# ACNode0_3.net
KiCad netlist of a schematic drawn in EAGLE
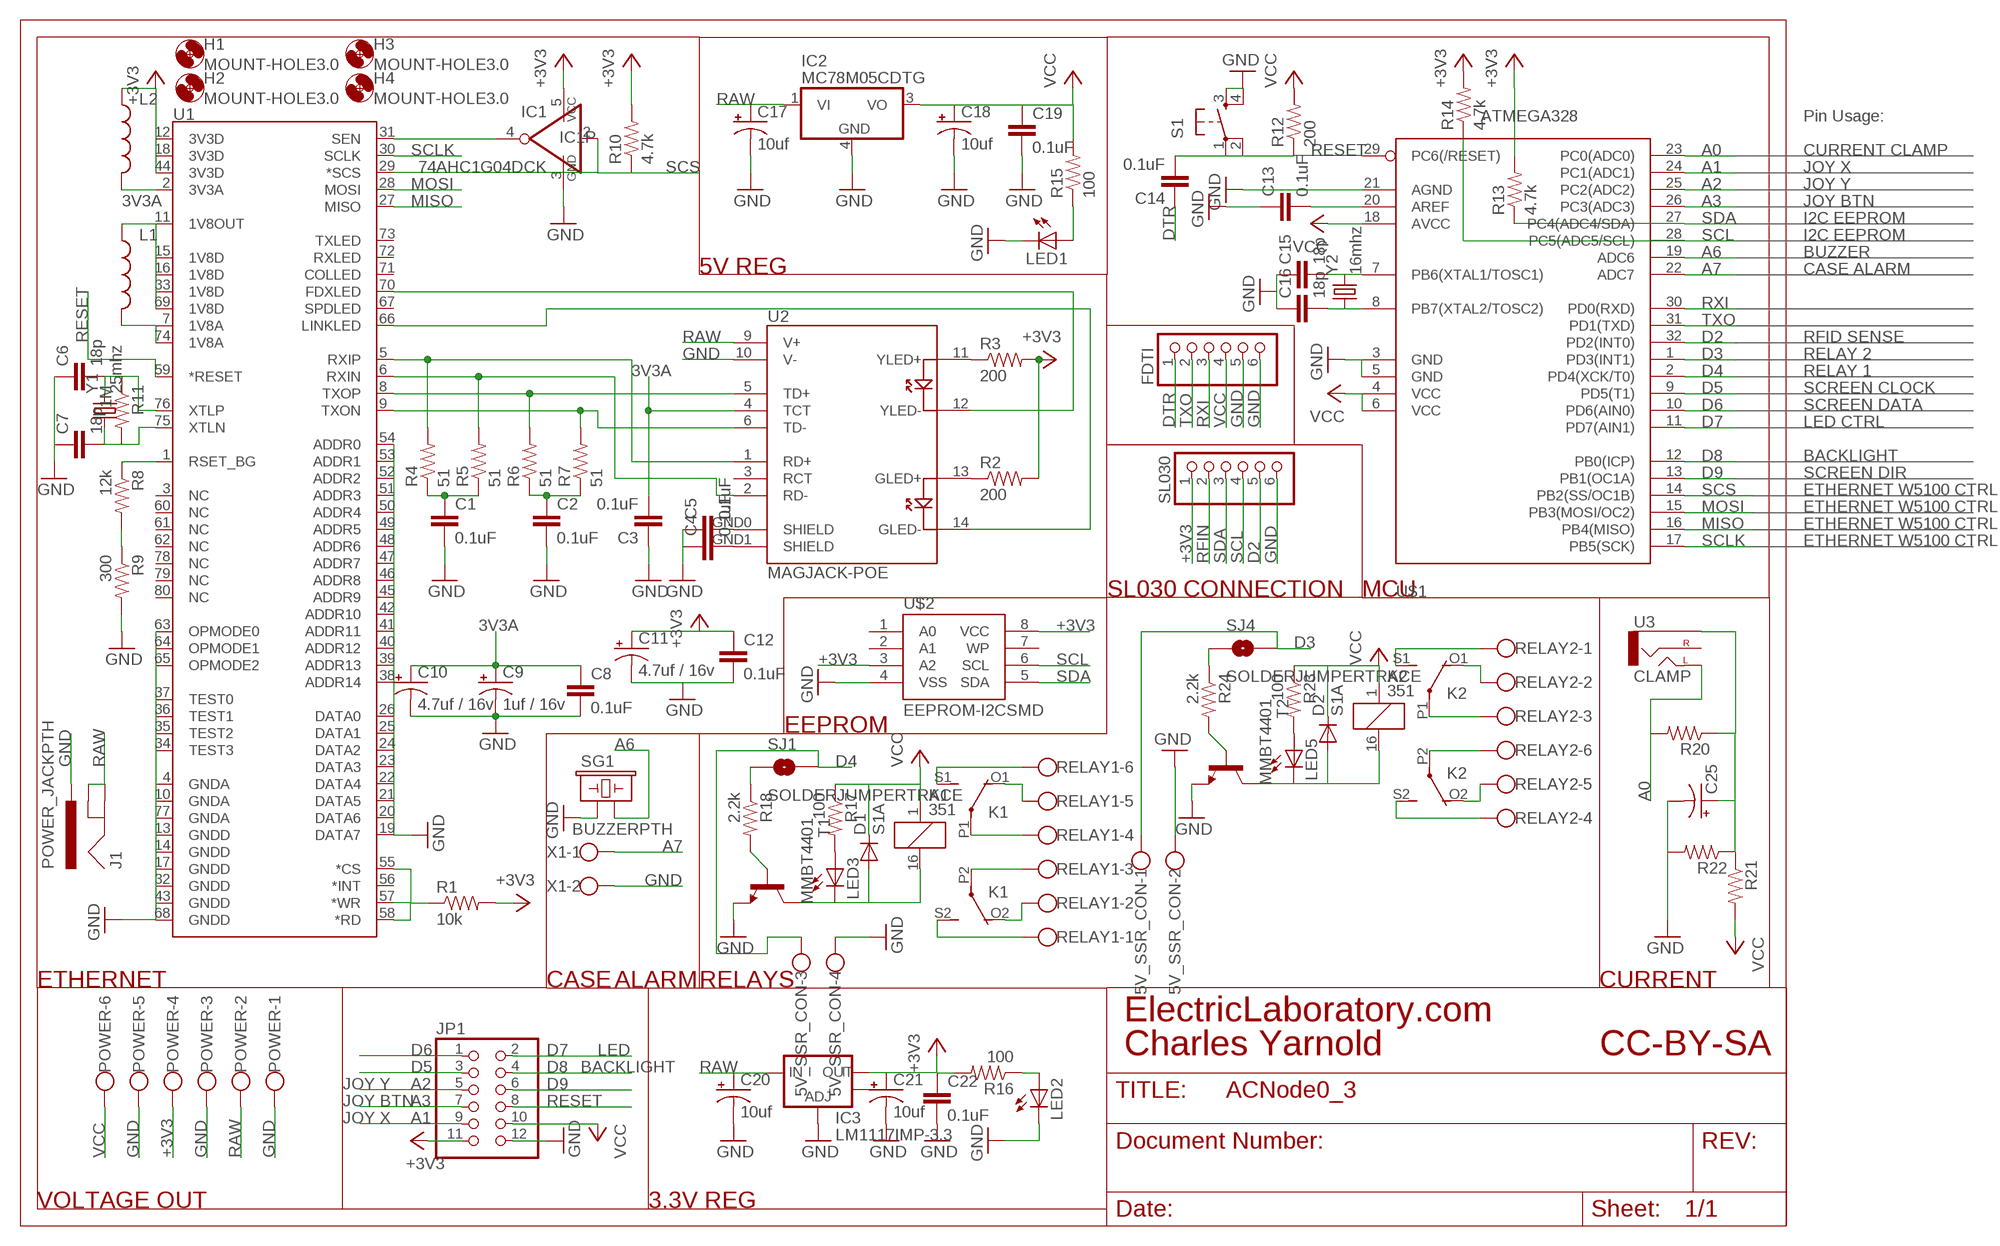
[diagram p0: schematic, sheet 1]

(export (version "E")
  (design (tool "Eeschema 10.0.6"))
  (components
    (comp (ref "5V_SSR_CON")
      (value "W237-4")
      (footprint "eagle-import:W237-4")
      (libsource (lib "eagle-import") (part "W237-4"))
    )
    (comp (ref "C1")
      (value "0.1uF")
      (footprint "eagle-import:0603-CAP")
      (libsource (lib "eagle-import") (part "CAP0603-CAP"))
    )
    (comp (ref "C2")
      (value "0.1uF")
      (footprint "eagle-import:0603-CAP")
      (libsource (lib "eagle-import") (part "CAP0603-CAP"))
    )
    (comp (ref "C3")
      (value "0.1uF")
      (footprint "eagle-import:0603-CAP")
      (libsource (lib "eagle-import") (part "CAP0603-CAP"))
    )
    (comp (ref "C4")
      (value "0.1uF")
      (footprint "eagle-import:0603-CAP")
      (libsource (lib "eagle-import") (part "CAP0603-CAP"))
    )
    (comp (ref "C5")
      (value "0.1uF")
      (footprint "eagle-import:0603-CAP")
      (libsource (lib "eagle-import") (part "CAP0603-CAP"))
    )
    (comp (ref "C6")
      (value "18p")
      (footprint "eagle-import:0603-CAP")
      (libsource (lib "eagle-import") (part "CAP0603-CAP"))
    )
    (comp (ref "C7")
      (value "18p")
      (footprint "eagle-import:0603-CAP")
      (libsource (lib "eagle-import") (part "CAP0603-CAP"))
    )
    (comp (ref "C8")
      (value "0.1uF")
      (footprint "eagle-import:0603-CAP")
      (libsource (lib "eagle-import") (part "CAP0603-CAP"))
    )
    (comp (ref "C9")
      (value "1uf / 16v")
      (footprint "eagle-import:EIA3216")
      (libsource (lib "eagle-import") (part "CAP_POL1206"))
    )
    (comp (ref "C10")
      (value "4.7uf / 16v")
      (footprint "eagle-import:EIA3216")
      (libsource (lib "eagle-import") (part "CAP_POL1206"))
    )
    (comp (ref "C11")
      (value "4.7uf / 16v")
      (footprint "eagle-import:EIA3216")
      (libsource (lib "eagle-import") (part "CAP_POL1206"))
    )
    (comp (ref "C12")
      (value "0.1uF")
      (footprint "eagle-import:0603-CAP")
      (libsource (lib "eagle-import") (part "CAP0603-CAP"))
    )
    (comp (ref "C13")
      (value "0.1uF")
      (footprint "eagle-import:0603-CAP")
      (libsource (lib "eagle-import") (part "CAP0603-CAP"))
    )
    (comp (ref "C14")
      (value "0.1uF")
      (footprint "eagle-import:0603-CAP")
      (libsource (lib "eagle-import") (part "CAP0603-CAP"))
    )
    (comp (ref "C15")
      (value "18p")
      (footprint "eagle-import:0603-CAP")
      (libsource (lib "eagle-import") (part "CAP0603-CAP"))
    )
    (comp (ref "C16")
      (value "18p")
      (footprint "eagle-import:0603-CAP")
      (libsource (lib "eagle-import") (part "CAP0603-CAP"))
    )
    (comp (ref "C17")
      (value "10uf")
      (footprint "eagle-import:EIA3216")
      (libsource (lib "eagle-import") (part "CAP_POL1206"))
    )
    (comp (ref "C18")
      (value "10uf")
      (footprint "eagle-import:EIA3216")
      (libsource (lib "eagle-import") (part "CAP_POL1206"))
    )
    (comp (ref "C19")
      (value "0.1uF")
      (footprint "eagle-import:0603-CAP")
      (libsource (lib "eagle-import") (part "CAP0603-CAP"))
    )
    (comp (ref "C20")
      (value "10uf")
      (footprint "eagle-import:EIA3216")
      (libsource (lib "eagle-import") (part "CAP_POL1206"))
    )
    (comp (ref "C21")
      (value "10uf")
      (footprint "eagle-import:EIA3216")
      (libsource (lib "eagle-import") (part "CAP_POL1206"))
    )
    (comp (ref "C22")
      (value "0.1uF")
      (footprint "eagle-import:0603-CAP")
      (libsource (lib "eagle-import") (part "CAP0603-CAP"))
    )
    (comp (ref "C25")
      (value "CAP_POL1206")
      (footprint "eagle-import:EIA3216")
      (libsource (lib "eagle-import") (part "CAP_POL1206"))
    )
    (comp (ref "D1")
      (value "S1A")
      (footprint "eagle-import:DO-214AC")
      (libsource (lib "eagle-import") (part "DIODE-DO-214AC"))
    )
    (comp (ref "D2")
      (value "S1A")
      (footprint "eagle-import:DO-214AC")
      (libsource (lib "eagle-import") (part "DIODE-DO-214AC"))
    )
    (comp (ref "FDTI")
      (value "PINHD-1X6")
      (footprint "eagle-import:1X06")
      (libsource (lib "eagle-import") (part "PINHD-1X6"))
    )
    (comp (ref "H1")
      (value "MOUNT-HOLE3.0")
      (footprint "eagle-import:3,0")
      (libsource (lib "eagle-import") (part "MOUNT-HOLE3.0"))
    )
    (comp (ref "H2")
      (value "MOUNT-HOLE3.0")
      (footprint "eagle-import:3,0")
      (libsource (lib "eagle-import") (part "MOUNT-HOLE3.0"))
    )
    (comp (ref "H3")
      (value "MOUNT-HOLE3.0")
      (footprint "eagle-import:3,0")
      (libsource (lib "eagle-import") (part "MOUNT-HOLE3.0"))
    )
    (comp (ref "H4")
      (value "MOUNT-HOLE3.0")
      (footprint "eagle-import:3,0")
      (libsource (lib "eagle-import") (part "MOUNT-HOLE3.0"))
    )
    (comp (ref "IC1")
      (value "74AHC1G04DCK")
      (footprint "eagle-import:SC70-5")
      (libsource (lib "eagle-import") (part "741G04DCKAHC"))
    )
    (comp (ref "IC2")
      (value "MC78M05CDTG")
      (footprint "eagle-import:DPACK_3")
      (libsource (lib "eagle-import") (part "MC78M05CDTG"))
    )
    (comp (ref "IC3")
      (value "LM1117IMP-3.3")
      (footprint "eagle-import:SOT223")
      (libsource (lib "eagle-import") (part "V_REG_LM1117SOT223"))
    )
    (comp (ref "J1")
      (value "POWER_JACKPTH")
      (footprint "eagle-import:POWER_JACK_PTH")
      (libsource (lib "eagle-import") (part "POWER_JACKPTH"))
    )
    (comp (ref "JP1")
      (value "PINHD-2X6")
      (footprint "eagle-import:2X06")
      (libsource (lib "eagle-import") (part "PINHD-2X6"))
    )
    (comp (ref "K1")
      (value "351")
      (footprint "eagle-import:351")
      (libsource (lib "eagle-import") (part "351"))
    )
    (comp (ref "K2")
      (value "351")
      (footprint "eagle-import:351")
      (libsource (lib "eagle-import") (part "351"))
    )
    (comp (ref "L1")
      (value "INDUCTOR1206H*")
      (footprint "eagle-import:INDUCTOR-1206")
      (libsource (lib "eagle-import") (part "INDUCTORH1206"))
    )
    (comp (ref "L2")
      (value "INDUCTOR1206H*")
      (footprint "eagle-import:INDUCTOR-1206")
      (libsource (lib "eagle-import") (part "INDUCTORH1206"))
    )
    (comp (ref "LED1")
      (value "LED0603")
      (footprint "eagle-import:LED-0603")
      (libsource (lib "eagle-import") (part "LED0603"))
    )
    (comp (ref "LED2")
      (value "LED0603")
      (footprint "eagle-import:LED-0603")
      (libsource (lib "eagle-import") (part "LED0603"))
    )
    (comp (ref "LED3")
      (value "LED0603")
      (footprint "eagle-import:LED-0603")
      (libsource (lib "eagle-import") (part "LED0603"))
    )
    (comp (ref "LED5")
      (value "LED0603")
      (footprint "eagle-import:LED-0603")
      (libsource (lib "eagle-import") (part "LED0603"))
    )
    (comp (ref "POWER")
      (value "W237-6")
      (footprint "eagle-import:W237-6")
      (libsource (lib "eagle-import") (part "W237-6"))
    )
    (comp (ref "R1")
      (value "10k")
      (footprint "eagle-import:0603-RES")
      (libsource (lib "eagle-import") (part "RESISTOR0603-RES"))
    )
    (comp (ref "R2")
      (value "200")
      (footprint "eagle-import:0603-RES")
      (libsource (lib "eagle-import") (part "RESISTOR0603-RES"))
    )
    (comp (ref "R3")
      (value "200")
      (footprint "eagle-import:0603-RES")
      (libsource (lib "eagle-import") (part "RESISTOR0603-RES"))
    )
    (comp (ref "R4")
      (value "51")
      (footprint "eagle-import:0603-RES")
      (libsource (lib "eagle-import") (part "RESISTOR0603-RES"))
    )
    (comp (ref "R5")
      (value "51")
      (footprint "eagle-import:0603-RES")
      (libsource (lib "eagle-import") (part "RESISTOR0603-RES"))
    )
    (comp (ref "R6")
      (value "51")
      (footprint "eagle-import:0603-RES")
      (libsource (lib "eagle-import") (part "RESISTOR0603-RES"))
    )
    (comp (ref "R7")
      (value "51")
      (footprint "eagle-import:0603-RES")
      (libsource (lib "eagle-import") (part "RESISTOR0603-RES"))
    )
    (comp (ref "R8")
      (value "12k")
      (footprint "eagle-import:0603-RES")
      (libsource (lib "eagle-import") (part "RESISTOR0603-RES"))
    )
    (comp (ref "R9")
      (value "300")
      (footprint "eagle-import:0603-RES")
      (libsource (lib "eagle-import") (part "RESISTOR0603-RES"))
    )
    (comp (ref "R10")
      (value "4.7k")
      (footprint "eagle-import:0603-RES")
      (libsource (lib "eagle-import") (part "RESISTOR0603-RES"))
    )
    (comp (ref "R11")
      (value "1M")
      (footprint "eagle-import:0603-RES")
      (libsource (lib "eagle-import") (part "RESISTOR0603-RES"))
    )
    (comp (ref "R12")
      (value "200")
      (footprint "eagle-import:0603-RES")
      (libsource (lib "eagle-import") (part "RESISTOR0603-RES"))
    )
    (comp (ref "R13")
      (value "4.7k")
      (footprint "eagle-import:0603-RES")
      (libsource (lib "eagle-import") (part "RESISTOR0603-RES"))
    )
    (comp (ref "R14")
      (value "4.7k")
      (footprint "eagle-import:0603-RES")
      (libsource (lib "eagle-import") (part "RESISTOR0603-RES"))
    )
    (comp (ref "R15")
      (value "100")
      (footprint "eagle-import:0603-RES")
      (libsource (lib "eagle-import") (part "RESISTOR0603-RES"))
    )
    (comp (ref "R16")
      (value "100")
      (footprint "eagle-import:0603-RES")
      (libsource (lib "eagle-import") (part "RESISTOR0603-RES"))
    )
    (comp (ref "R17")
      (value "100")
      (footprint "eagle-import:0603-RES")
      (libsource (lib "eagle-import") (part "RESISTOR0603-RES"))
    )
    (comp (ref "R18")
      (value "2.2k")
      (footprint "eagle-import:0603-RES")
      (libsource (lib "eagle-import") (part "RESISTOR0603-RES"))
    )
    (comp (ref "R20")
      (value "RESISTOR0603-RES")
      (footprint "eagle-import:0603-RES")
      (libsource (lib "eagle-import") (part "RESISTOR0603-RES"))
    )
    (comp (ref "R21")
      (value "RESISTOR0603-RES")
      (footprint "eagle-import:0603-RES")
      (libsource (lib "eagle-import") (part "RESISTOR0603-RES"))
    )
    (comp (ref "R22")
      (value "RESISTOR0603-RES")
      (footprint "eagle-import:0603-RES")
      (libsource (lib "eagle-import") (part "RESISTOR0603-RES"))
    )
    (comp (ref "R23")
      (value "100")
      (footprint "eagle-import:0603-RES")
      (libsource (lib "eagle-import") (part "RESISTOR0603-RES"))
    )
    (comp (ref "R24")
      (value "2.2k")
      (footprint "eagle-import:0603-RES")
      (libsource (lib "eagle-import") (part "RESISTOR0603-RES"))
    )
    (comp (ref "RELAY1")
      (value "W237-6")
      (footprint "eagle-import:W237-6")
      (libsource (lib "eagle-import") (part "W237-6"))
    )
    (comp (ref "RELAY2")
      (value "W237-6")
      (footprint "eagle-import:W237-6")
      (libsource (lib "eagle-import") (part "W237-6"))
    )
    (comp (ref "S1")
      (value "TAC_SWITCHSMD")
      (footprint "eagle-import:TACTILE_SWITCH_SMD")
      (libsource (lib "eagle-import") (part "TAC_SWITCHSMD"))
    )
    (comp (ref "SG1")
      (value "BUZZERPTH")
      (footprint "eagle-import:BUZZER-12MM")
      (libsource (lib "eagle-import") (part "BUZZERPTH"))
    )
    (comp (ref "SJ1")
      (value "SOLDERJUMPERTRACE")
      (footprint "eagle-import:SJ_2S-TRACE")
      (libsource (lib "eagle-import") (part "SOLDERJUMPERTRACE"))
    )
    (comp (ref "SJ4")
      (value "SOLDERJUMPERTRACE")
      (footprint "eagle-import:SJ_2S-TRACE")
      (libsource (lib "eagle-import") (part "SOLDERJUMPERTRACE"))
    )
    (comp (ref "SL030")
      (value "PINHD-1X6")
      (footprint "eagle-import:1X06")
      (libsource (lib "eagle-import") (part "PINHD-1X6"))
    )
    (comp (ref "T1")
      (value "MMBT4401")
      (footprint "eagle-import:SOT23-BEC")
      (libsource (lib "eagle-import") (part "-NPN-SOT23-BECMMBT4401LT1"))
    )
    (comp (ref "T2")
      (value "MMBT4401")
      (footprint "eagle-import:SOT23-BEC")
      (libsource (lib "eagle-import") (part "-NPN-SOT23-BECMMBT4401LT1"))
    )
    (comp (ref "U$1")
      (value "ATMEGA328")
      (footprint "eagle-import:TQFP32-08")
      (libsource (lib "eagle-import") (part "AVR-MEGA8-AI"))
    )
    (comp (ref "U$2")
      (value "EEPROM-I2CSMD")
      (footprint "eagle-import:SO08")
      (libsource (lib "eagle-import") (part "EEPROM-I2CSMD"))
    )
    (comp (ref "U1")
      (value "W5100")
      (footprint "eagle-import:LQFP-80")
      (libsource (lib "eagle-import") (part "W5100"))
    )
    (comp (ref "U2")
      (value "MAGJACK-POE")
      (footprint "eagle-import:MAGJACK-POE")
      (libsource (lib "eagle-import") (part "MAGJACK-POE"))
    )
    (comp (ref "U3")
      (value "CLAMP")
      (footprint "eagle-import:AUDIO-JACK")
      (libsource (lib "eagle-import") (part "AUDIO-JACKPTH"))
    )
    (comp (ref "X1")
      (value "W237-102")
      (footprint "eagle-import:W237-102")
      (fields (field (name "MPN") "237-102"))
      (libsource (lib "eagle-import") (part "W237-102"))
    )
    (comp (ref "Y1")
      (value "25mhz")
      (footprint "eagle-import:HC49UP")
      (libsource (lib "eagle-import") (part "CRYSTALSMD"))
    )
    (comp (ref "Y2")
      (value "16mhz")
      (footprint "eagle-import:HC49UP")
      (libsource (lib "eagle-import") (part "CRYSTALSMD"))
    )
  )
  (nets
    (net (code "1") (name "+3V3") (class "Default")
      (node (ref "C11") (pin "A") (pinfunction "+_A") (pintype "passive"))
      (node (ref "C12") (pin "1") (pinfunction "1_1") (pintype "passive"))
      (node (ref "C21") (pin "A") (pinfunction "+_A") (pintype "passive"))
      (node (ref "C22") (pin "1") (pinfunction "1_1") (pintype "passive"))
      (node (ref "IC1") (pin "5") (pinfunction "VCC_5") (pintype "power_in"))
      (node (ref "IC3") (pin "2") (pinfunction "OUT_2") (pintype "output"))
      (node (ref "JP1") (pin "11") (pinfunction "11_11") (pintype "passive"))
      (node (ref "L2") (pin "P$1") (pinfunction "1_P$1") (pintype "passive"))
      (node (ref "POWER") (pin "4") (pinfunction "KL_4") (pintype "passive"))
      (node (ref "R1") (pin "2") (pinfunction "2_2") (pintype "passive"))
      (node (ref "R10") (pin "2") (pinfunction "2_2") (pintype "passive"))
      (node (ref "R13") (pin "2") (pinfunction "2_2") (pintype "passive"))
      (node (ref "R14") (pin "2") (pinfunction "2_2") (pintype "passive"))
      (node (ref "R16") (pin "2") (pinfunction "2_2") (pintype "passive"))
      (node (ref "R2") (pin "2") (pinfunction "2_2") (pintype "passive"))
      (node (ref "R3") (pin "2") (pinfunction "2_2") (pintype "passive"))
      (node (ref "SL030") (pin "1") (pinfunction "1_1") (pintype "passive"))
      (node (ref "U$2") (pin "3") (pinfunction "A2_3") (pintype "bidirectional"))
      (node (ref "U$2") (pin "8") (pinfunction "VCC_8") (pintype "power_in"))
      (node (ref "U1") (pin "12") (pinfunction "3V3D_12") (pintype "bidirectional"))
      (node (ref "U1") (pin "18") (pinfunction "3V3D_18") (pintype "bidirectional"))
      (node (ref "U1") (pin "44") (pinfunction "3V3D_44") (pintype "bidirectional"))
    )
    (net (code "2") (name "/3V3A") (class "Default")
      (node (ref "C10") (pin "A") (pinfunction "+_A") (pintype "passive"))
      (node (ref "C3") (pin "2") (pinfunction "2_2") (pintype "passive"))
      (node (ref "C8") (pin "1") (pinfunction "1_1") (pintype "passive"))
      (node (ref "C9") (pin "A") (pinfunction "+_A") (pintype "passive"))
      (node (ref "L2") (pin "P$2") (pinfunction "2_P$2") (pintype "passive"))
      (node (ref "U1") (pin "2") (pinfunction "3V3A_2") (pintype "bidirectional"))
      (node (ref "U2") (pin "4") (pinfunction "TCT_4") (pintype "bidirectional"))
    )
    (net (code "3") (name "/A0") (class "Default")
      (node (ref "R20") (pin "2") (pinfunction "2_2") (pintype "passive"))
      (node (ref "U$1") (pin "23") (pinfunction "PC0(ADC0)_23") (pintype "bidirectional"))
      (node (ref "U3") (pin "TIP") (pinfunction "LEFT_TIP") (pintype "bidirectional"))
    )
    (net (code "4") (name "/A1") (class "Default")
      (node (ref "JP1") (pin "9") (pinfunction "9_9") (pintype "passive"))
      (node (ref "U$1") (pin "24") (pinfunction "PC1(ADC1)_24") (pintype "bidirectional"))
    )
    (net (code "5") (name "/A2") (class "Default")
      (node (ref "JP1") (pin "5") (pinfunction "5_5") (pintype "passive"))
      (node (ref "U$1") (pin "25") (pinfunction "PC2(ADC2)_25") (pintype "bidirectional"))
    )
    (net (code "6") (name "/A3") (class "Default")
      (node (ref "JP1") (pin "7") (pinfunction "7_7") (pintype "passive"))
      (node (ref "U$1") (pin "26") (pinfunction "PC3(ADC3)_26") (pintype "bidirectional"))
    )
    (net (code "7") (name "/A6") (class "Default")
      (node (ref "SG1") (pin "-") (pinfunction "2_-") (pintype "passive"))
      (node (ref "U$1") (pin "19") (pinfunction "ADC6_19") (pintype "bidirectional"))
    )
    (net (code "8") (name "/A7") (class "Default")
      (node (ref "U$1") (pin "22") (pinfunction "ADC7_22") (pintype "bidirectional"))
      (node (ref "X1") (pin "1") (pinfunction "KL_1") (pintype "passive"))
    )
    (net (code "9") (name "/D2") (class "Default")
      (node (ref "SL030") (pin "5") (pinfunction "5_5") (pintype "passive"))
      (node (ref "U$1") (pin "32") (pinfunction "PD2(INT0)_32") (pintype "bidirectional"))
    )
    (net (code "10") (name "/D3") (class "Default")
      (node (ref "5V_SSR_CON") (pin "1") (pinfunction "KL_1") (pintype "passive"))
      (node (ref "SJ4") (pin "2") (pinfunction "2_2") (pintype "passive"))
      (node (ref "U$1") (pin "1") (pinfunction "PD3(INT1)_1") (pintype "bidirectional"))
    )
    (net (code "11") (name "/D4") (class "Default")
      (node (ref "5V_SSR_CON") (pin "3") (pinfunction "KL_3") (pintype "passive"))
      (node (ref "SJ1") (pin "2") (pinfunction "2_2") (pintype "passive"))
      (node (ref "U$1") (pin "2") (pinfunction "PD4(XCK/T0)_2") (pintype "bidirectional"))
    )
    (net (code "12") (name "/D5") (class "Default")
      (node (ref "JP1") (pin "3") (pinfunction "3_3") (pintype "passive"))
      (node (ref "U$1") (pin "9") (pinfunction "PD5(T1)_9") (pintype "bidirectional"))
    )
    (net (code "13") (name "/D6") (class "Default")
      (node (ref "JP1") (pin "1") (pinfunction "1_1") (pintype "passive"))
      (node (ref "U$1") (pin "10") (pinfunction "PD6(AIN0)_10") (pintype "bidirectional"))
    )
    (net (code "14") (name "/D7") (class "Default")
      (node (ref "JP1") (pin "2") (pinfunction "2_2") (pintype "passive"))
      (node (ref "U$1") (pin "11") (pinfunction "PD7(AIN1)_11") (pintype "bidirectional"))
    )
    (net (code "15") (name "/D8") (class "Default")
      (node (ref "JP1") (pin "4") (pinfunction "4_4") (pintype "passive"))
      (node (ref "U$1") (pin "12") (pinfunction "PB0(ICP)_12") (pintype "bidirectional"))
    )
    (net (code "16") (name "/D9") (class "Default")
      (node (ref "JP1") (pin "6") (pinfunction "6_6") (pintype "passive"))
      (node (ref "U$1") (pin "13") (pinfunction "PB1(OC1A)_13") (pintype "bidirectional"))
    )
    (net (code "17") (name "/DTR") (class "Default")
      (node (ref "C14") (pin "1") (pinfunction "1_1") (pintype "passive"))
      (node (ref "FDTI") (pin "1") (pinfunction "1_1") (pintype "passive"))
    )
    (net (code "18") (name "/MISO") (class "Default")
      (node (ref "U$1") (pin "16") (pinfunction "PB4(MISO)_16") (pintype "bidirectional"))
      (node (ref "U1") (pin "27") (pinfunction "MISO_27") (pintype "bidirectional"))
    )
    (net (code "19") (name "/MOSI") (class "Default")
      (node (ref "U$1") (pin "15") (pinfunction "PB3(MOSI/OC2)_15") (pintype "bidirectional"))
      (node (ref "U1") (pin "28") (pinfunction "MOSI_28") (pintype "bidirectional"))
    )
    (net (code "20") (name "/RAW") (class "Default")
      (node (ref "C17") (pin "A") (pinfunction "+_A") (pintype "passive"))
      (node (ref "C20") (pin "A") (pinfunction "+_A") (pintype "passive"))
      (node (ref "IC2") (pin "1") (pinfunction "VI_1") (pintype "input"))
      (node (ref "IC3") (pin "3") (pinfunction "IN_3") (pintype "input"))
      (node (ref "J1") (pin "GND") (pinfunction "GND_GND") (pintype "bidirectional"))
      (node (ref "J1") (pin "GNDBREAK") (pinfunction "GNDBREAK_GNDBREAK") (pintype "bidirectional"))
      (node (ref "POWER") (pin "2") (pinfunction "KL_2") (pintype "passive"))
      (node (ref "U2") (pin "9") (pinfunction "V+_9") (pintype "bidirectional"))
    )
    (net (code "21") (name "/RESET") (class "Default")
      (node (ref "C14") (pin "2") (pinfunction "2_2") (pintype "passive"))
      (node (ref "JP1") (pin "8") (pinfunction "8_8") (pintype "passive"))
      (node (ref "R12") (pin "1") (pinfunction "1_1") (pintype "passive"))
      (node (ref "S1") (pin "1") (pinfunction "1_1") (pintype "passive"))
      (node (ref "S1") (pin "2") (pinfunction "2_2") (pintype "passive"))
      (node (ref "U$1") (pin "29") (pinfunction "PC6(/RESET)_29") (pintype "bidirectional"))
      (node (ref "U1") (pin "59") (pinfunction "*RESET_59") (pintype "bidirectional"))
    )
    (net (code "22") (name "/RFIN") (class "Default")
      (node (ref "SL030") (pin "2") (pinfunction "2_2") (pintype "passive"))
    )
    (net (code "23") (name "/RXI") (class "Default")
      (node (ref "FDTI") (pin "3") (pinfunction "3_3") (pintype "passive"))
      (node (ref "U$1") (pin "30") (pinfunction "PD0(RXD)_30") (pintype "bidirectional"))
    )
    (net (code "24") (name "/SCL") (class "Default")
      (node (ref "R14") (pin "1") (pinfunction "1_1") (pintype "passive"))
      (node (ref "SL030") (pin "4") (pinfunction "4_4") (pintype "passive"))
      (node (ref "U$1") (pin "28") (pinfunction "PC5(ADC5/SCL)_28") (pintype "bidirectional"))
      (node (ref "U$2") (pin "6") (pinfunction "SCL_6") (pintype "bidirectional"))
    )
    (net (code "25") (name "/SCLK") (class "Default")
      (node (ref "U$1") (pin "17") (pinfunction "PB5(SCK)_17") (pintype "bidirectional"))
      (node (ref "U1") (pin "30") (pinfunction "SCLK_30") (pintype "bidirectional"))
    )
    (net (code "26") (name "/SCS") (class "Default")
      (node (ref "IC1") (pin "2") (pinfunction "I_2") (pintype "input"))
      (node (ref "R10") (pin "1") (pinfunction "1_1") (pintype "passive"))
      (node (ref "U$1") (pin "14") (pinfunction "PB2(SS/OC1B)_14") (pintype "bidirectional"))
      (node (ref "U1") (pin "29") (pinfunction "*SCS_29") (pintype "bidirectional"))
    )
    (net (code "27") (name "/SDA") (class "Default")
      (node (ref "R13") (pin "1") (pinfunction "1_1") (pintype "passive"))
      (node (ref "SL030") (pin "3") (pinfunction "3_3") (pintype "passive"))
      (node (ref "U$1") (pin "27") (pinfunction "PC4(ADC4/SDA)_27") (pintype "bidirectional"))
      (node (ref "U$2") (pin "5") (pinfunction "SDA_5") (pintype "bidirectional"))
    )
    (net (code "28") (name "/TXO") (class "Default")
      (node (ref "FDTI") (pin "2") (pinfunction "2_2") (pintype "passive"))
      (node (ref "U$1") (pin "31") (pinfunction "PD1(TXD)_31") (pintype "bidirectional"))
    )
    (net (code "29") (name "GND") (class "Default")
      (node (ref "5V_SSR_CON") (pin "2") (pinfunction "KL_2") (pintype "passive"))
      (node (ref "5V_SSR_CON") (pin "4") (pinfunction "KL_4") (pintype "passive"))
      (node (ref "C1") (pin "2") (pinfunction "2_2") (pintype "passive"))
      (node (ref "C10") (pin "C") (pinfunction "-_C") (pintype "passive"))
      (node (ref "C11") (pin "C") (pinfunction "-_C") (pintype "passive"))
      (node (ref "C12") (pin "2") (pinfunction "2_2") (pintype "passive"))
      (node (ref "C13") (pin "1") (pinfunction "1_1") (pintype "passive"))
      (node (ref "C15") (pin "1") (pinfunction "1_1") (pintype "passive"))
      (node (ref "C16") (pin "1") (pinfunction "1_1") (pintype "passive"))
      (node (ref "C17") (pin "C") (pinfunction "-_C") (pintype "passive"))
      (node (ref "C18") (pin "C") (pinfunction "-_C") (pintype "passive"))
      (node (ref "C19") (pin "2") (pinfunction "2_2") (pintype "passive"))
      (node (ref "C2") (pin "2") (pinfunction "2_2") (pintype "passive"))
      (node (ref "C20") (pin "C") (pinfunction "-_C") (pintype "passive"))
      (node (ref "C21") (pin "C") (pinfunction "-_C") (pintype "passive"))
      (node (ref "C22") (pin "2") (pinfunction "2_2") (pintype "passive"))
      (node (ref "C25") (pin "C") (pinfunction "-_C") (pintype "passive"))
      (node (ref "C3") (pin "1") (pinfunction "1_1") (pintype "passive"))
      (node (ref "C4") (pin "1") (pinfunction "1_1") (pintype "passive"))
      (node (ref "C5") (pin "1") (pinfunction "1_1") (pintype "passive"))
      (node (ref "C6") (pin "1") (pinfunction "1_1") (pintype "passive"))
      (node (ref "C7") (pin "1") (pinfunction "1_1") (pintype "passive"))
      (node (ref "C8") (pin "2") (pinfunction "2_2") (pintype "passive"))
      (node (ref "C9") (pin "C") (pinfunction "-_C") (pintype "passive"))
      (node (ref "FDTI") (pin "5") (pinfunction "5_5") (pintype "passive"))
      (node (ref "FDTI") (pin "6") (pinfunction "6_6") (pintype "passive"))
      (node (ref "IC1") (pin "3") (pinfunction "GND_3") (pintype "power_in"))
      (node (ref "IC2") (pin "4") (pinfunction "GND_4") (pintype "passive"))
      (node (ref "IC3") (pin "1") (pinfunction "ADJ_1") (pintype "input"))
      (node (ref "J1") (pin "PWR") (pinfunction "PWR_PWR") (pintype "bidirectional"))
      (node (ref "JP1") (pin "12") (pinfunction "12_12") (pintype "passive"))
      (node (ref "LED1") (pin "C") (pinfunction "C_C") (pintype "passive"))
      (node (ref "LED2") (pin "C") (pinfunction "C_C") (pintype "passive"))
      (node (ref "POWER") (pin "1") (pinfunction "KL_1") (pintype "passive"))
      (node (ref "POWER") (pin "3") (pinfunction "KL_3") (pintype "passive"))
      (node (ref "POWER") (pin "5") (pinfunction "KL_5") (pintype "passive"))
      (node (ref "R22") (pin "2") (pinfunction "2_2") (pintype "passive"))
      (node (ref "R9") (pin "2") (pinfunction "2_2") (pintype "passive"))
      (node (ref "S1") (pin "3") (pinfunction "3_3") (pintype "passive"))
      (node (ref "S1") (pin "4") (pinfunction "4_4") (pintype "passive"))
      (node (ref "SG1") (pin "+") (pinfunction "1_+") (pintype "passive"))
      (node (ref "SL030") (pin "6") (pinfunction "6_6") (pintype "passive"))
      (node (ref "T1") (pin "E") (pinfunction "E_E") (pintype "passive"))
      (node (ref "T2") (pin "E") (pinfunction "E_E") (pintype "passive"))
      (node (ref "U$1") (pin "21") (pinfunction "AGND_21") (pintype "bidirectional"))
      (node (ref "U$1") (pin "3") (pinfunction "GND_3") (pintype "bidirectional"))
      (node (ref "U$1") (pin "5") (pinfunction "GND_5") (pintype "bidirectional"))
      (node (ref "U$2") (pin "4") (pinfunction "VSS_4") (pintype "power_in"))
      (node (ref "U1") (pin "10") (pinfunction "GNDA_10") (pintype "bidirectional"))
      (node (ref "U1") (pin "13") (pinfunction "GNDD_13") (pintype "bidirectional"))
      (node (ref "U1") (pin "14") (pinfunction "GNDD_14") (pintype "bidirectional"))
      (node (ref "U1") (pin "17") (pinfunction "GNDD_17") (pintype "bidirectional"))
      (node (ref "U1") (pin "19") (pinfunction "DATA7_19") (pintype "bidirectional"))
      (node (ref "U1") (pin "20") (pinfunction "DATA6_20") (pintype "bidirectional"))
      (node (ref "U1") (pin "21") (pinfunction "DATA5_21") (pintype "bidirectional"))
      (node (ref "U1") (pin "22") (pinfunction "DATA4_22") (pintype "bidirectional"))
      (node (ref "U1") (pin "23") (pinfunction "DATA3_23") (pintype "bidirectional"))
      (node (ref "U1") (pin "24") (pinfunction "DATA2_24") (pintype "bidirectional"))
      (node (ref "U1") (pin "25") (pinfunction "DATA1_25") (pintype "bidirectional"))
      (node (ref "U1") (pin "26") (pinfunction "DATA0_26") (pintype "bidirectional"))
      (node (ref "U1") (pin "32") (pinfunction "GNDD_32") (pintype "bidirectional"))
      (node (ref "U1") (pin "34") (pinfunction "TEST3_34") (pintype "bidirectional"))
      (node (ref "U1") (pin "35") (pinfunction "TEST2_35") (pintype "bidirectional"))
      (node (ref "U1") (pin "36") (pinfunction "TEST1_36") (pintype "bidirectional"))
      (node (ref "U1") (pin "37") (pinfunction "TEST0_37") (pintype "bidirectional"))
      (node (ref "U1") (pin "38") (pinfunction "ADDR14_38") (pintype "bidirectional"))
      (node (ref "U1") (pin "39") (pinfunction "ADDR13_39") (pintype "bidirectional"))
      (node (ref "U1") (pin "4") (pinfunction "GNDA_4") (pintype "bidirectional"))
      (node (ref "U1") (pin "40") (pinfunction "ADDR12_40") (pintype "bidirectional"))
      (node (ref "U1") (pin "41") (pinfunction "ADDR11_41") (pintype "bidirectional"))
      (node (ref "U1") (pin "42") (pinfunction "ADDR10_42") (pintype "bidirectional"))
      (node (ref "U1") (pin "43") (pinfunction "GNDD_43") (pintype "bidirectional"))
      (node (ref "U1") (pin "45") (pinfunction "ADDR9_45") (pintype "bidirectional"))
      (node (ref "U1") (pin "46") (pinfunction "ADDR8_46") (pintype "bidirectional"))
      (node (ref "U1") (pin "47") (pinfunction "ADDR7_47") (pintype "bidirectional"))
      (node (ref "U1") (pin "48") (pinfunction "ADDR6_48") (pintype "bidirectional"))
      (node (ref "U1") (pin "49") (pinfunction "ADDR5_49") (pintype "bidirectional"))
      (node (ref "U1") (pin "50") (pinfunction "ADDR4_50") (pintype "bidirectional"))
      (node (ref "U1") (pin "51") (pinfunction "ADDR3_51") (pintype "bidirectional"))
      (node (ref "U1") (pin "52") (pinfunction "ADDR2_52") (pintype "bidirectional"))
      (node (ref "U1") (pin "53") (pinfunction "ADDR1_53") (pintype "bidirectional"))
      (node (ref "U1") (pin "54") (pinfunction "ADDR0_54") (pintype "bidirectional"))
      (node (ref "U1") (pin "63") (pinfunction "OPMODE0_63") (pintype "bidirectional"))
      (node (ref "U1") (pin "64") (pinfunction "OPMODE1_64") (pintype "bidirectional"))
      (node (ref "U1") (pin "65") (pinfunction "OPMODE2_65") (pintype "bidirectional"))
      (node (ref "U1") (pin "68") (pinfunction "GNDD_68") (pintype "bidirectional"))
      (node (ref "U1") (pin "77") (pinfunction "GNDA_77") (pintype "bidirectional"))
      (node (ref "U2") (pin "10") (pinfunction "V-_10") (pintype "bidirectional"))
      (node (ref "X1") (pin "2") (pinfunction "KL_2") (pintype "passive"))
    )
    (net (code "30") (name "Net-(C1-Pad1)") (class "Default")
      (node (ref "C1") (pin "1") (pinfunction "1_1") (pintype "passive"))
      (node (ref "R4") (pin "1") (pinfunction "1_1") (pintype "passive"))
      (node (ref "R5") (pin "1") (pinfunction "1_1") (pintype "passive"))
    )
    (net (code "31") (name "Net-(C2-Pad1)") (class "Default")
      (node (ref "C2") (pin "1") (pinfunction "1_1") (pintype "passive"))
      (node (ref "R6") (pin "1") (pinfunction "1_1") (pintype "passive"))
      (node (ref "R7") (pin "1") (pinfunction "1_1") (pintype "passive"))
    )
    (net (code "32") (name "Net-(C4-Pad2)") (class "Default")
      (node (ref "C4") (pin "2") (pinfunction "2_2") (pintype "passive"))
      (node (ref "U2") (pin "GND1") (pinfunction "SHIELD_GND1") (pintype "bidirectional"))
    )
    (net (code "33") (name "Net-(C5-Pad2)") (class "Default")
      (node (ref "C5") (pin "2") (pinfunction "2_2") (pintype "passive"))
      (node (ref "U2") (pin "GND0") (pinfunction "SHIELD_GND0") (pintype "bidirectional"))
    )
    (net (code "34") (name "Net-(C25-+)") (class "Default")
      (node (ref "C25") (pin "A") (pinfunction "+_A") (pintype "passive"))
      (node (ref "R20") (pin "1") (pinfunction "1_1") (pintype "passive"))
      (node (ref "R21") (pin "1") (pinfunction "1_1") (pintype "passive"))
      (node (ref "R22") (pin "1") (pinfunction "1_1") (pintype "passive"))
      (node (ref "U3") (pin "SLEEVE") (pinfunction "SLEEVE_SLEEVE") (pintype "bidirectional"))
    )
    (net (code "35") (name "Net-(IC1A-O)") (class "Default")
      (node (ref "IC1") (pin "4") (pinfunction "O_4") (pintype "output"))
      (node (ref "U1") (pin "31") (pinfunction "SEN_31") (pintype "bidirectional"))
    )
    (net (code "36") (name "Net-(K1A-2)") (class "Default")
      (node (ref "D1") (pin "A") (pinfunction "A_A") (pintype "passive"))
      (node (ref "K1") (pin "16") (pinfunction "2_16") (pintype "passive"))
      (node (ref "LED3") (pin "C") (pinfunction "C_C") (pintype "passive"))
      (node (ref "T1") (pin "C") (pinfunction "C_C") (pintype "passive"))
    )
    (net (code "37") (name "Net-(K1B-O)") (class "Default")
      (node (ref "K1") (pin "O1") (pinfunction "O_O1") (pintype "passive"))
      (node (ref "RELAY1") (pin "5") (pinfunction "KL_5") (pintype "passive"))
    )
    (net (code "38") (name "Net-(K1B-P)") (class "Default")
      (node (ref "K1") (pin "P1") (pinfunction "P_P1") (pintype "passive"))
      (node (ref "RELAY1") (pin "4") (pinfunction "KL_4") (pintype "passive"))
    )
    (net (code "39") (name "Net-(K1B-S)") (class "Default")
      (node (ref "K1") (pin "S1") (pinfunction "S_S1") (pintype "passive"))
      (node (ref "RELAY1") (pin "6") (pinfunction "KL_6") (pintype "passive"))
    )
    (net (code "40") (name "Net-(K1C-O)") (class "Default")
      (node (ref "K1") (pin "O2") (pinfunction "O_O2") (pintype "passive"))
      (node (ref "RELAY1") (pin "2") (pinfunction "KL_2") (pintype "passive"))
    )
    (net (code "41") (name "Net-(K1C-P)") (class "Default")
      (node (ref "K1") (pin "P2") (pinfunction "P_P2") (pintype "passive"))
      (node (ref "RELAY1") (pin "3") (pinfunction "KL_3") (pintype "passive"))
    )
    (net (code "42") (name "Net-(K1C-S)") (class "Default")
      (node (ref "K1") (pin "S2") (pinfunction "S_S2") (pintype "passive"))
      (node (ref "RELAY1") (pin "1") (pinfunction "KL_1") (pintype "passive"))
    )
    (net (code "43") (name "Net-(K2A-2)") (class "Default")
      (node (ref "D2") (pin "A") (pinfunction "A_A") (pintype "passive"))
      (node (ref "K2") (pin "16") (pinfunction "2_16") (pintype "passive"))
      (node (ref "LED5") (pin "C") (pinfunction "C_C") (pintype "passive"))
      (node (ref "T2") (pin "C") (pinfunction "C_C") (pintype "passive"))
    )
    (net (code "44") (name "Net-(K2B-O)") (class "Default")
      (node (ref "K2") (pin "O1") (pinfunction "O_O1") (pintype "passive"))
      (node (ref "RELAY2") (pin "2") (pinfunction "KL_2") (pintype "passive"))
    )
    (net (code "45") (name "Net-(K2B-P)") (class "Default")
      (node (ref "K2") (pin "P1") (pinfunction "P_P1") (pintype "passive"))
      (node (ref "RELAY2") (pin "3") (pinfunction "KL_3") (pintype "passive"))
    )
    (net (code "46") (name "Net-(K2B-S)") (class "Default")
      (node (ref "K2") (pin "S1") (pinfunction "S_S1") (pintype "passive"))
      (node (ref "RELAY2") (pin "1") (pinfunction "KL_1") (pintype "passive"))
    )
    (net (code "47") (name "Net-(K2C-O)") (class "Default")
      (node (ref "K2") (pin "O2") (pinfunction "O_O2") (pintype "passive"))
      (node (ref "RELAY2") (pin "5") (pinfunction "KL_5") (pintype "passive"))
    )
    (net (code "48") (name "Net-(K2C-P)") (class "Default")
      (node (ref "K2") (pin "P2") (pinfunction "P_P2") (pintype "passive"))
      (node (ref "RELAY2") (pin "6") (pinfunction "KL_6") (pintype "passive"))
    )
    (net (code "49") (name "Net-(K2C-S)") (class "Default")
      (node (ref "K2") (pin "S2") (pinfunction "S_S2") (pintype "passive"))
      (node (ref "RELAY2") (pin "4") (pinfunction "KL_4") (pintype "passive"))
    )
    (net (code "50") (name "Net-(L1-1)") (class "Default")
      (node (ref "L1") (pin "P$1") (pinfunction "1_P$1") (pintype "passive"))
      (node (ref "U1") (pin "11") (pinfunction "1V8OUT_11") (pintype "bidirectional"))
      (node (ref "U1") (pin "15") (pinfunction "1V8D_15") (pintype "bidirectional"))
      (node (ref "U1") (pin "16") (pinfunction "1V8D_16") (pintype "bidirectional"))
      (node (ref "U1") (pin "33") (pinfunction "1V8D_33") (pintype "bidirectional"))
      (node (ref "U1") (pin "69") (pinfunction "1V8D_69") (pintype "bidirectional"))
    )
    (net (code "51") (name "Net-(L1-2)") (class "Default")
      (node (ref "L1") (pin "P$2") (pinfunction "2_P$2") (pintype "passive"))
      (node (ref "U1") (pin "7") (pinfunction "1V8A_7") (pintype "bidirectional"))
      (node (ref "U1") (pin "74") (pinfunction "1V8A_74") (pintype "bidirectional"))
    )
    (net (code "52") (name "Net-(LED1-PadA)") (class "Default")
      (node (ref "LED1") (pin "A") (pinfunction "A_A") (pintype "passive"))
      (node (ref "R15") (pin "1") (pinfunction "1_1") (pintype "passive"))
    )
    (net (code "53") (name "Net-(LED2-PadA)") (class "Default")
      (node (ref "LED2") (pin "A") (pinfunction "A_A") (pintype "passive"))
      (node (ref "R16") (pin "1") (pinfunction "1_1") (pintype "passive"))
    )
    (net (code "54") (name "Net-(LED3-PadA)") (class "Default")
      (node (ref "LED3") (pin "A") (pinfunction "A_A") (pintype "passive"))
      (node (ref "R17") (pin "2") (pinfunction "2_2") (pintype "passive"))
    )
    (net (code "55") (name "Net-(LED5-PadA)") (class "Default")
      (node (ref "LED5") (pin "A") (pinfunction "A_A") (pintype "passive"))
      (node (ref "R23") (pin "2") (pinfunction "2_2") (pintype "passive"))
    )
    (net (code "56") (name "Net-(R8-Pad2)") (class "Default")
      (node (ref "R8") (pin "2") (pinfunction "2_2") (pintype "passive"))
      (node (ref "R9") (pin "1") (pinfunction "1_1") (pintype "passive"))
    )
    (net (code "57") (name "Net-(R18-Pad1)") (class "Default")
      (node (ref "R18") (pin "1") (pinfunction "1_1") (pintype "passive"))
      (node (ref "SJ1") (pin "1") (pinfunction "1_1") (pintype "passive"))
    )
    (net (code "58") (name "Net-(R18-Pad2)") (class "Default")
      (node (ref "R18") (pin "2") (pinfunction "2_2") (pintype "passive"))
      (node (ref "T1") (pin "B") (pinfunction "B_B") (pintype "passive"))
    )
    (net (code "59") (name "Net-(R24-Pad1)") (class "Default")
      (node (ref "R24") (pin "1") (pinfunction "1_1") (pintype "passive"))
      (node (ref "SJ4") (pin "1") (pinfunction "1_1") (pintype "passive"))
    )
    (net (code "60") (name "Net-(R24-Pad2)") (class "Default")
      (node (ref "R24") (pin "2") (pinfunction "2_2") (pintype "passive"))
      (node (ref "T2") (pin "B") (pinfunction "B_B") (pintype "passive"))
    )
    (net (code "61") (name "Net-(U$1-AREF)") (class "Default")
      (node (ref "C13") (pin "2") (pinfunction "2_2") (pintype "passive"))
      (node (ref "U$1") (pin "20") (pinfunction "AREF_20") (pintype "bidirectional"))
    )
    (net (code "62") (name "Net-(U$1-PB6(XTAL1{slash}TOSC1))") (class "Default")
      (node (ref "C15") (pin "2") (pinfunction "2_2") (pintype "passive"))
      (node (ref "U$1") (pin "7") (pinfunction "PB6(XTAL1/TOSC1)_7") (pintype "bidirectional"))
      (node (ref "Y2") (pin "2") (pinfunction "2_2") (pintype "passive"))
    )
    (net (code "63") (name "Net-(U$1-PB7(XTAL2{slash}TOSC2))") (class "Default")
      (node (ref "C16") (pin "2") (pinfunction "2_2") (pintype "passive"))
      (node (ref "U$1") (pin "8") (pinfunction "PB7(XTAL2/TOSC2)_8") (pintype "bidirectional"))
      (node (ref "Y2") (pin "1") (pinfunction "1_1") (pintype "passive"))
    )
    (net (code "64") (name "Net-(U1-*CS)") (class "Default")
      (node (ref "R1") (pin "1") (pinfunction "1_1") (pintype "passive"))
      (node (ref "U1") (pin "55") (pinfunction "*CS_55") (pintype "bidirectional"))
      (node (ref "U1") (pin "57") (pinfunction "*WR_57") (pintype "bidirectional"))
      (node (ref "U1") (pin "58") (pinfunction "*RD_58") (pintype "bidirectional"))
    )
    (net (code "65") (name "Net-(U1-FDXLED)") (class "Default")
      (node (ref "U1") (pin "70") (pinfunction "FDXLED_70") (pintype "bidirectional"))
      (node (ref "U2") (pin "12") (pinfunction "YLED-_12") (pintype "bidirectional"))
    )
    (net (code "66") (name "Net-(U1-LINKLED)") (class "Default")
      (node (ref "U1") (pin "66") (pinfunction "LINKLED_66") (pintype "bidirectional"))
      (node (ref "U2") (pin "14") (pinfunction "GLED-_14") (pintype "bidirectional"))
    )
    (net (code "67") (name "Net-(U1-RSET_BG)") (class "Default")
      (node (ref "R8") (pin "1") (pinfunction "1_1") (pintype "passive"))
      (node (ref "U1") (pin "1") (pinfunction "RSET_BG_1") (pintype "bidirectional"))
    )
    (net (code "68") (name "Net-(U1-RXIN)") (class "Default")
      (node (ref "R5") (pin "2") (pinfunction "2_2") (pintype "passive"))
      (node (ref "U1") (pin "6") (pinfunction "RXIN_6") (pintype "bidirectional"))
      (node (ref "U2") (pin "2") (pinfunction "RD-_2") (pintype "bidirectional"))
    )
    (net (code "69") (name "Net-(U1-RXIP)") (class "Default")
      (node (ref "R4") (pin "2") (pinfunction "2_2") (pintype "passive"))
      (node (ref "U1") (pin "5") (pinfunction "RXIP_5") (pintype "bidirectional"))
      (node (ref "U2") (pin "1") (pinfunction "RD+_1") (pintype "bidirectional"))
    )
    (net (code "70") (name "Net-(U1-TXON)") (class "Default")
      (node (ref "R7") (pin "2") (pinfunction "2_2") (pintype "passive"))
      (node (ref "U1") (pin "9") (pinfunction "TXON_9") (pintype "bidirectional"))
      (node (ref "U2") (pin "6") (pinfunction "TD-_6") (pintype "bidirectional"))
    )
    (net (code "71") (name "Net-(U1-TXOP)") (class "Default")
      (node (ref "R6") (pin "2") (pinfunction "2_2") (pintype "passive"))
      (node (ref "U1") (pin "8") (pinfunction "TXOP_8") (pintype "bidirectional"))
      (node (ref "U2") (pin "5") (pinfunction "TD+_5") (pintype "bidirectional"))
    )
    (net (code "72") (name "Net-(U1-XTLN)") (class "Default")
      (node (ref "C7") (pin "2") (pinfunction "2_2") (pintype "passive"))
      (node (ref "R11") (pin "2") (pinfunction "2_2") (pintype "passive"))
      (node (ref "U1") (pin "75") (pinfunction "XTLN_75") (pintype "bidirectional"))
      (node (ref "Y1") (pin "1") (pinfunction "1_1") (pintype "passive"))
    )
    (net (code "73") (name "Net-(U1-XTLP)") (class "Default")
      (node (ref "C6") (pin "2") (pinfunction "2_2") (pintype "passive"))
      (node (ref "R11") (pin "1") (pinfunction "1_1") (pintype "passive"))
      (node (ref "U1") (pin "76") (pinfunction "XTLP_76") (pintype "bidirectional"))
      (node (ref "Y1") (pin "2") (pinfunction "2_2") (pintype "passive"))
    )
    (net (code "74") (name "Net-(U2-GLED+)") (class "Default")
      (node (ref "R2") (pin "1") (pinfunction "1_1") (pintype "passive"))
      (node (ref "U2") (pin "13") (pinfunction "GLED+_13") (pintype "bidirectional"))
    )
    (net (code "75") (name "Net-(U2-YLED+)") (class "Default")
      (node (ref "R3") (pin "1") (pinfunction "1_1") (pintype "passive"))
      (node (ref "U2") (pin "11") (pinfunction "YLED+_11") (pintype "bidirectional"))
    )
    (net (code "76") (name "VCC") (class "Default")
      (node (ref "C18") (pin "A") (pinfunction "+_A") (pintype "passive"))
      (node (ref "C19") (pin "1") (pinfunction "1_1") (pintype "passive"))
      (node (ref "D1") (pin "C") (pinfunction "C_C") (pintype "passive"))
      (node (ref "D2") (pin "C") (pinfunction "C_C") (pintype "passive"))
      (node (ref "FDTI") (pin "4") (pinfunction "4_4") (pintype "passive"))
      (node (ref "IC2") (pin "3") (pinfunction "VO_3") (pintype "passive"))
      (node (ref "JP1") (pin "10") (pinfunction "10_10") (pintype "passive"))
      (node (ref "K1") (pin "1") (pinfunction "1_1") (pintype "passive"))
      (node (ref "K2") (pin "1") (pinfunction "1_1") (pintype "passive"))
      (node (ref "POWER") (pin "6") (pinfunction "KL_6") (pintype "passive"))
      (node (ref "R12") (pin "2") (pinfunction "2_2") (pintype "passive"))
      (node (ref "R15") (pin "2") (pinfunction "2_2") (pintype "passive"))
      (node (ref "R17") (pin "1") (pinfunction "1_1") (pintype "passive"))
      (node (ref "R21") (pin "2") (pinfunction "2_2") (pintype "passive"))
      (node (ref "R23") (pin "1") (pinfunction "1_1") (pintype "passive"))
      (node (ref "U$1") (pin "18") (pinfunction "AVCC_18") (pintype "bidirectional"))
      (node (ref "U$1") (pin "4") (pinfunction "VCC_4") (pintype "bidirectional"))
      (node (ref "U$1") (pin "6") (pinfunction "VCC_6") (pintype "bidirectional"))
    )
    (net (code "77") (name "unconnected-(IC3-OUT-Pad4)") (class "Default")
      (node (ref "IC3") (pin "4") (pinfunction "OUT_4") (pintype "output"))
    )
    (net (code "78") (name "unconnected-(U$2-A0-Pad1)") (class "Default")
      (node (ref "U$2") (pin "1") (pinfunction "A0_1") (pintype "bidirectional"))
    )
    (net (code "79") (name "unconnected-(U$2-A1-Pad2)") (class "Default")
      (node (ref "U$2") (pin "2") (pinfunction "A1_2") (pintype "bidirectional"))
    )
    (net (code "80") (name "unconnected-(U$2-WP-Pad7)") (class "Default")
      (node (ref "U$2") (pin "7") (pinfunction "WP_7") (pintype "bidirectional"))
    )
    (net (code "81") (name "unconnected-(U1-*INT-Pad56)") (class "Default")
      (node (ref "U1") (pin "56") (pinfunction "*INT_56") (pintype "bidirectional"))
    )
    (net (code "82") (name "unconnected-(U1-COLLED-Pad71)") (class "Default")
      (node (ref "U1") (pin "71") (pinfunction "COLLED_71") (pintype "bidirectional"))
    )
    (net (code "83") (name "unconnected-(U1-NC-Pad3)") (class "Default")
      (node (ref "U1") (pin "3") (pinfunction "NC_3") (pintype "bidirectional"))
    )
    (net (code "84") (name "unconnected-(U1-NC-Pad60)") (class "Default")
      (node (ref "U1") (pin "60") (pinfunction "NC_60") (pintype "bidirectional"))
    )
    (net (code "85") (name "unconnected-(U1-NC-Pad61)") (class "Default")
      (node (ref "U1") (pin "61") (pinfunction "NC_61") (pintype "bidirectional"))
    )
    (net (code "86") (name "unconnected-(U1-NC-Pad62)") (class "Default")
      (node (ref "U1") (pin "62") (pinfunction "NC_62") (pintype "bidirectional"))
    )
    (net (code "87") (name "unconnected-(U1-NC-Pad78)") (class "Default")
      (node (ref "U1") (pin "78") (pinfunction "NC_78") (pintype "bidirectional"))
    )
    (net (code "88") (name "unconnected-(U1-NC-Pad79)") (class "Default")
      (node (ref "U1") (pin "79") (pinfunction "NC_79") (pintype "bidirectional"))
    )
    (net (code "89") (name "unconnected-(U1-NC-Pad80)") (class "Default")
      (node (ref "U1") (pin "80") (pinfunction "NC_80") (pintype "bidirectional"))
    )
    (net (code "90") (name "unconnected-(U1-RXLED-Pad72)") (class "Default")
      (node (ref "U1") (pin "72") (pinfunction "RXLED_72") (pintype "bidirectional"))
    )
    (net (code "91") (name "unconnected-(U1-SPDLED-Pad67)") (class "Default")
      (node (ref "U1") (pin "67") (pinfunction "SPDLED_67") (pintype "bidirectional"))
    )
    (net (code "92") (name "unconnected-(U1-TXLED-Pad73)") (class "Default")
      (node (ref "U1") (pin "73") (pinfunction "TXLED_73") (pintype "bidirectional"))
    )
    (net (code "93") (name "unconnected-(U2-RCT-Pad3)") (class "Default")
      (node (ref "U2") (pin "3") (pinfunction "RCT_3") (pintype "bidirectional"))
    )
    (net (code "94") (name "unconnected-(U3-RIGHT-PadRING)") (class "Default")
      (node (ref "U3") (pin "RING") (pinfunction "RIGHT_RING") (pintype "bidirectional"))
    )
  )
)
